# ESP12Breakout.net
KiCad netlist of a schematic drawn in EAGLE
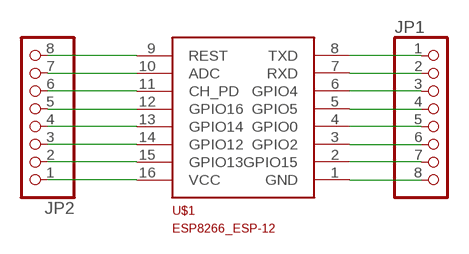
[diagram p0: schematic, sheet 1]

(export (version "E")
  (design (tool "Eeschema 10.0.6"))
  (components
    (comp (ref "JP1")
      (value "PINHD-1X8")
      (footprint "eagle-import:1X08")
      (libsource (lib "eagle-import") (part "PINHD-1X8"))
    )
    (comp (ref "JP2")
      (value "PINHD-1X8")
      (footprint "eagle-import:1X08")
      (libsource (lib "eagle-import") (part "PINHD-1X8"))
    )
    (comp (ref "U$1")
      (value "ESP8266_ESP-12")
      (footprint "eagle-import:ESP8266-ESP12")
      (libsource (lib "eagle-import") (part "ESP8266_ESP-12"))
    )
  )
  (nets
    (net (code "1") (name "Net-(U$1-ADC)") (class "Default")
      (node (ref "JP2") (pin "7") (pinfunction "7_7") (pintype "passive"))
      (node (ref "U$1") (pin "10") (pinfunction "ADC_10") (pintype "bidirectional"))
    )
    (net (code "2") (name "Net-(U$1-CH_PD)") (class "Default")
      (node (ref "JP2") (pin "6") (pinfunction "6_6") (pintype "passive"))
      (node (ref "U$1") (pin "11") (pinfunction "CH_PD_11") (pintype "bidirectional"))
    )
    (net (code "3") (name "Net-(U$1-GND)") (class "Default")
      (node (ref "JP1") (pin "8") (pinfunction "8_8") (pintype "passive"))
      (node (ref "U$1") (pin "1") (pinfunction "GND_1") (pintype "bidirectional"))
    )
    (net (code "4") (name "Net-(U$1-GPIO0)") (class "Default")
      (node (ref "JP1") (pin "5") (pinfunction "5_5") (pintype "passive"))
      (node (ref "U$1") (pin "4") (pinfunction "GPIO0_4") (pintype "bidirectional"))
    )
    (net (code "5") (name "Net-(U$1-GPIO2)") (class "Default")
      (node (ref "JP1") (pin "6") (pinfunction "6_6") (pintype "passive"))
      (node (ref "U$1") (pin "3") (pinfunction "GPIO2_3") (pintype "bidirectional"))
    )
    (net (code "6") (name "Net-(U$1-GPIO4)") (class "Default")
      (node (ref "JP1") (pin "3") (pinfunction "3_3") (pintype "passive"))
      (node (ref "U$1") (pin "6") (pinfunction "GPIO4_6") (pintype "bidirectional"))
    )
    (net (code "7") (name "Net-(U$1-GPIO5)") (class "Default")
      (node (ref "JP1") (pin "4") (pinfunction "4_4") (pintype "passive"))
      (node (ref "U$1") (pin "5") (pinfunction "GPIO5_5") (pintype "bidirectional"))
    )
    (net (code "8") (name "Net-(U$1-GPIO12)") (class "Default")
      (node (ref "JP2") (pin "3") (pinfunction "3_3") (pintype "passive"))
      (node (ref "U$1") (pin "14") (pinfunction "GPIO12_14") (pintype "bidirectional"))
    )
    (net (code "9") (name "Net-(U$1-GPIO13)") (class "Default")
      (node (ref "JP2") (pin "2") (pinfunction "2_2") (pintype "passive"))
      (node (ref "U$1") (pin "15") (pinfunction "GPIO13_15") (pintype "bidirectional"))
    )
    (net (code "10") (name "Net-(U$1-GPIO14)") (class "Default")
      (node (ref "JP2") (pin "4") (pinfunction "4_4") (pintype "passive"))
      (node (ref "U$1") (pin "13") (pinfunction "GPIO14_13") (pintype "bidirectional"))
    )
    (net (code "11") (name "Net-(U$1-GPIO15)") (class "Default")
      (node (ref "JP1") (pin "7") (pinfunction "7_7") (pintype "passive"))
      (node (ref "U$1") (pin "2") (pinfunction "GPIO15_2") (pintype "bidirectional"))
    )
    (net (code "12") (name "Net-(U$1-GPIO16)") (class "Default")
      (node (ref "JP2") (pin "5") (pinfunction "5_5") (pintype "passive"))
      (node (ref "U$1") (pin "12") (pinfunction "GPIO16_12") (pintype "bidirectional"))
    )
    (net (code "13") (name "Net-(U$1-REST)") (class "Default")
      (node (ref "JP2") (pin "8") (pinfunction "8_8") (pintype "passive"))
      (node (ref "U$1") (pin "9") (pinfunction "REST_9") (pintype "bidirectional"))
    )
    (net (code "14") (name "Net-(U$1-RXD)") (class "Default")
      (node (ref "JP1") (pin "2") (pinfunction "2_2") (pintype "passive"))
      (node (ref "U$1") (pin "7") (pinfunction "RXD_7") (pintype "bidirectional"))
    )
    (net (code "15") (name "Net-(U$1-TXD)") (class "Default")
      (node (ref "JP1") (pin "1") (pinfunction "1_1") (pintype "passive"))
      (node (ref "U$1") (pin "8") (pinfunction "TXD_8") (pintype "bidirectional"))
    )
    (net (code "16") (name "Net-(U$1-VCC)") (class "Default")
      (node (ref "JP2") (pin "1") (pinfunction "1_1") (pintype "passive"))
      (node (ref "U$1") (pin "16") (pinfunction "VCC_16") (pintype "bidirectional"))
    )
  )
)
